# MAIN.net
KiCad netlist of a schematic drawn in Altium Designer
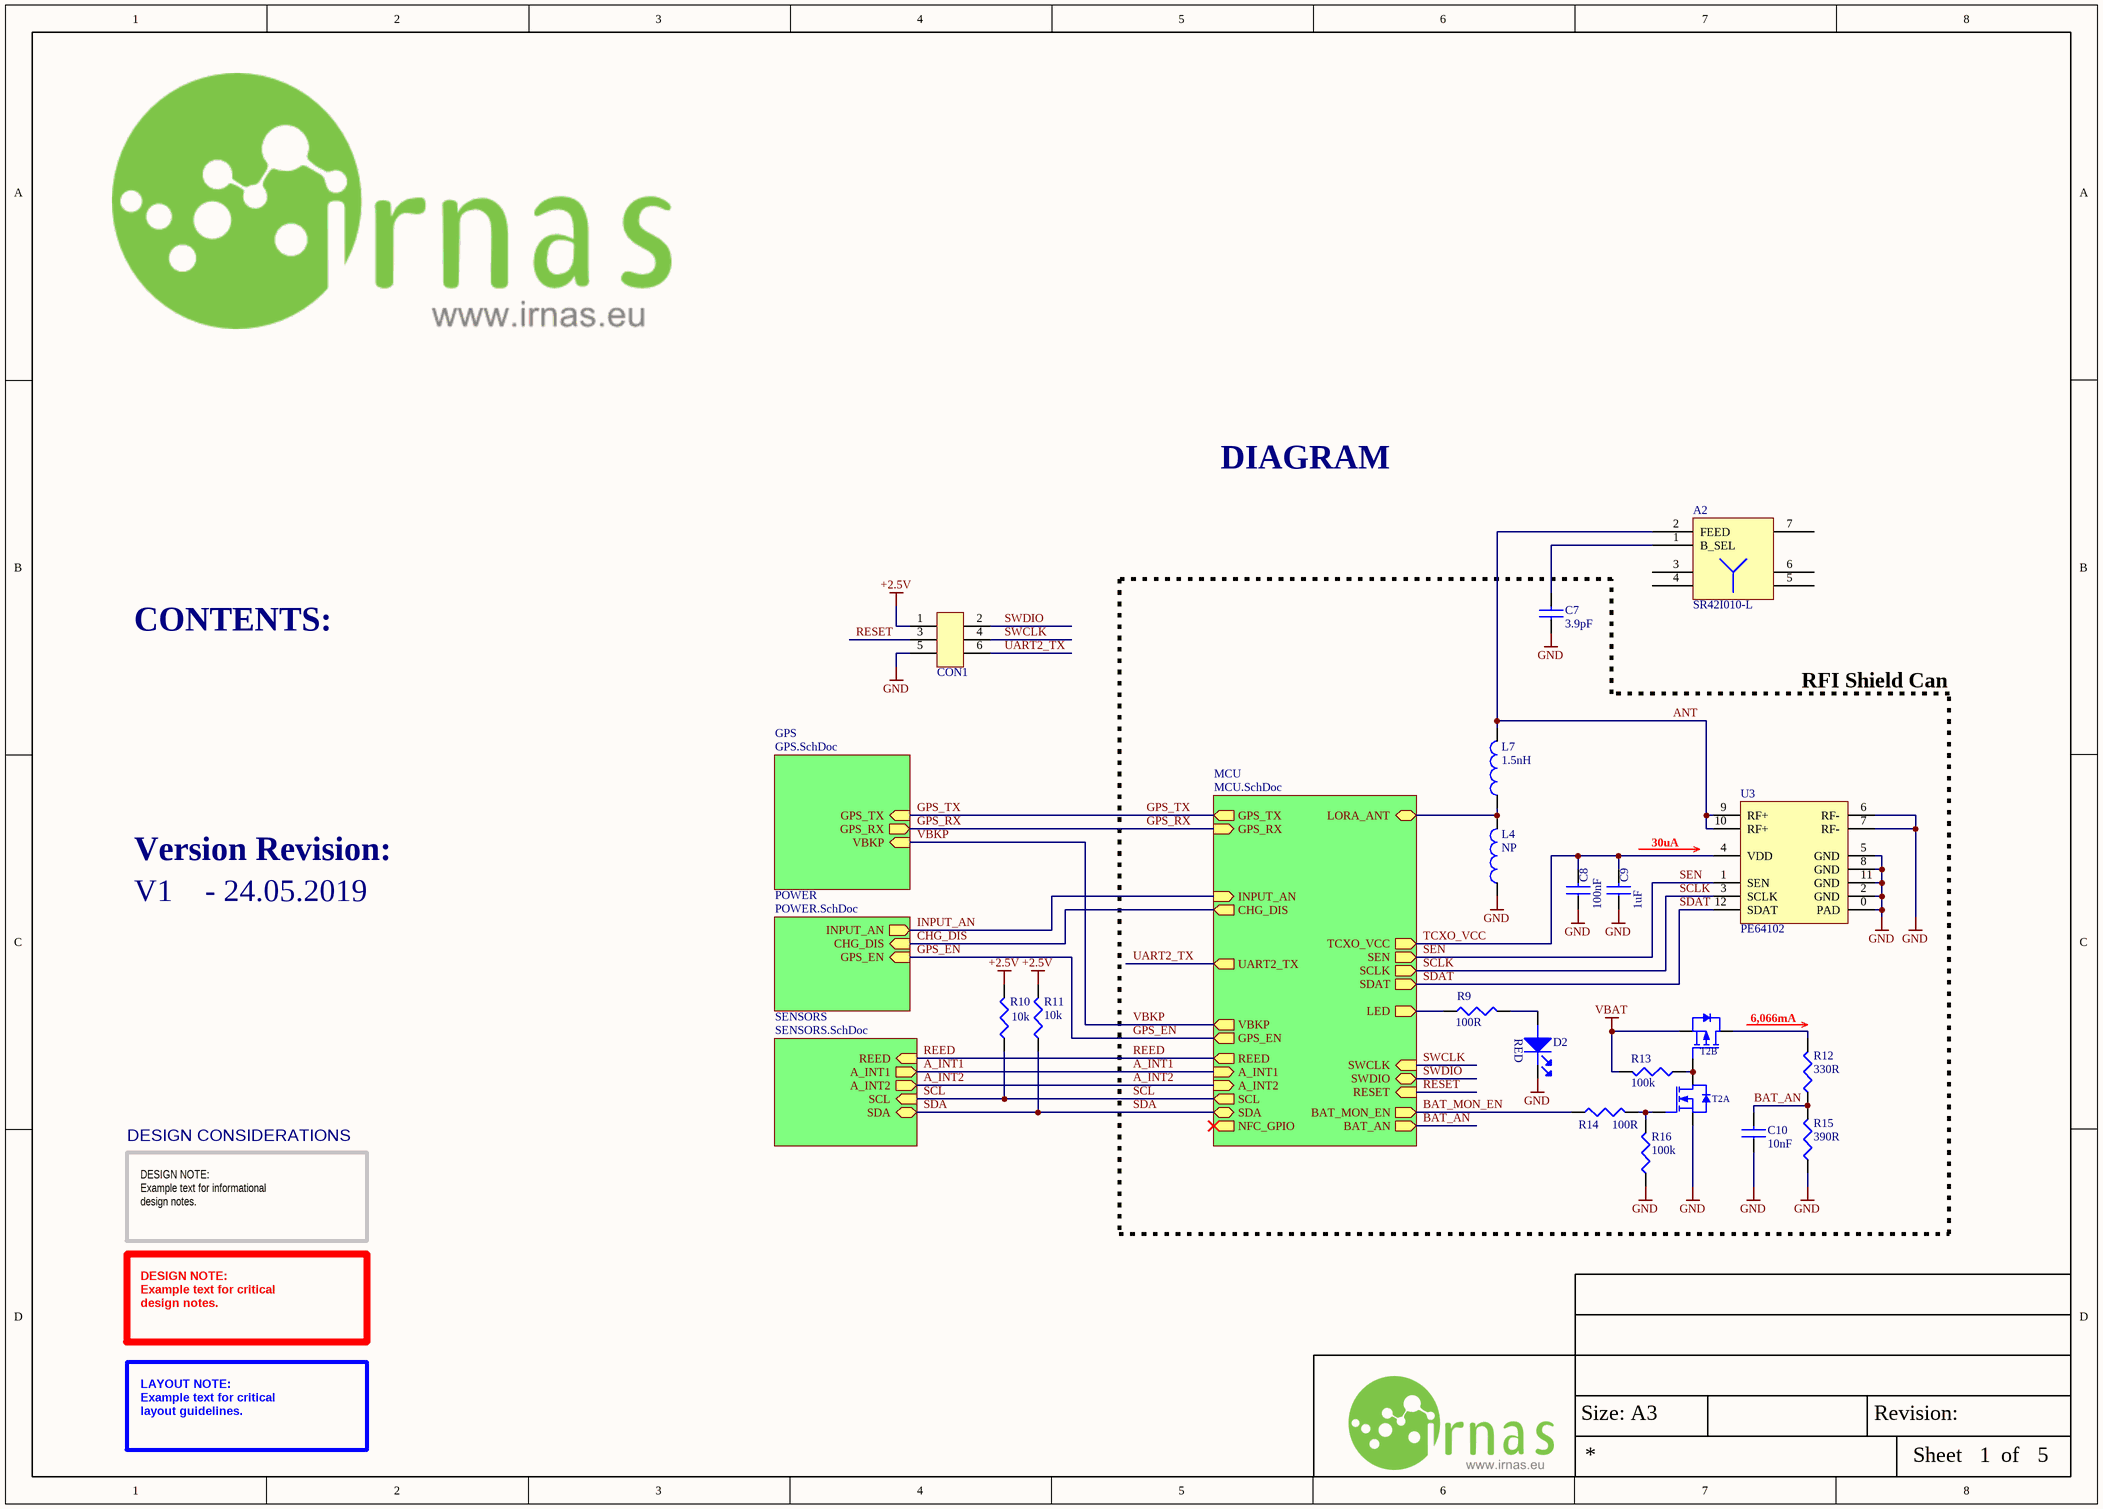
[diagram p0: MAIN.SchDoc]

(export (version "E")
  (design (tool "Eeschema 10.0.6"))
  (components
    (comp (ref "A2")
      (value "SR42I010-L")
      (footprint "SR42I010-L")
      (description "Antenna SMD -4dBi Gain 870MHz/928MHz Automotive 7-Pin SMD T/R")
      (fields (field (name "MANUFACTURER") "Antenova") (field (name "MANUFACTURER PART NUMBER") "SR42I010-R"))
      (libsource (lib "Passive") (part "ANT - SR42I010-L"))
    )
    (comp (ref "C7")
      (value "3.9pF")
      (footprint "CAP0402")
      (description "3.9 pF, 50 V, 0402 [1005 Metric], ± 0.25pF, NP0")
      (fields
        (field (name "MANUFACTURER") "KEMET")
        (field (name "MANUFACTURER PART NUMBER") "MC0402N3R9C500CT")
      )
      (libsource (lib "Passive") (part "C - 3.9pF/0402"))
    )
    (comp (ref "C8")
      (value "100nF")
      (footprint "CAP0402")
      (description "0.1 F, 16 V,  5%, X5R, MC Series")
      (fields
        (field (name "MANUFACTURER") "Multicomp")
        (field (name "MANUFACTURER PART NUMBER") "MC0402X104J160CT")
      )
      (libsource (lib "Passive") (part "C - 100nF/0402"))
    )
    (comp (ref "C9")
      (value "1uF")
      (footprint "CAP0402")
      (description "CAP CER 1UF 10V 20% X5R 0402")
      (fields
        (field (name "MANUFACTURER") "Murata")
        (field (name "MANUFACTURER PART NUMBER") "GRM155R61A105ME15D")
      )
      (libsource (lib "Passive") (part "C - 1uF/0402"))
    )
    (comp (ref "C10")
      (value "10nF")
      (footprint "CAP0402")
      (description "CAP CER 10000PF 16V X7R 0402")
      (fields
        (field (name "MANUFACTURER") "Murata")
        (field (name "MANUFACTURER PART NUMBER") "GRM155R71C103KA01D")
      )
      (libsource (lib "Passive") (part "C - 10nF/0402"))
    )
    (comp (ref "CON1")
      (value "Tag connect")
      (footprint "TC2030-IDC-NL")
      (libsource (lib "Connectors") (part "tag connecot 6 pin"))
    )
    (comp (ref "D2")
      (value "LED RED")
      (footprint "LED0603")
      (description "BROADCOM LIMITED - HSMS-C190 - LED, RED, 10MCD, 626NM")
      (fields
        (field (name "MANUFACTURER") "BROADCOM LIMITED")
        (field (name "MANUFACTURER PART NUMBER") "HSMS-C190")
      )
      (libsource (lib "Active") (part "LED - LED RED"))
    )
    (comp (ref "L4")
      (value "NP")
      (footprint "IND0402")
      (description "Inductor RF Chip Multi-Layer 4.3nH 0.3nH 100MHz 8Q-Factor Air 300mA 210mOhm DCR 0402 Paper T/R")
      (fields
        (field (name "MANUFACTURER") "Murata")
        (field (name "MANUFACTURER PART NUMBER") "LQG15HN4N3S02D")
      )
      (libsource (lib "Passive") (part "L - 4.3nH/0402"))
    )
    (comp (ref "L7")
      (value "1.5nH")
      (footprint "IND0402")
      (description "1.5 nH, LQG15HS_02 Series, 1 A, 0402")
      (fields
        (field (name "MANUFACTURER") "Murata")
        (field (name "MANUFACTURER PART NUMBER") "LQG15HS1N5S02D")
      )
      (libsource (lib "Passive") (part "L - 1.5nH/0402"))
    )
    (comp (ref "R9")
      (value "100R")
      (footprint "RES0402")
      (description "100 ohm, 50 V, 0402 [1005 Metric], 62.5 mW,  1%")
      (fields
        (field (name "MANUFACTURER") "Multicomp")
        (field (name "MANUFACTURER PART NUMBER") "MCMR04X1000FTL")
      )
      (libsource (lib "Passive") (part "R - 100R/0402"))
    )
    (comp (ref "R10")
      (value "10k")
      (footprint "RES0402")
      (description "10 kohm, 50 V, 0402 [1005 Metric], 62.5 mW,  1%, MCWR Series")
      (fields
        (field (name "MANUFACTURER") "Multicomp")
        (field (name "MANUFACTURER PART NUMBER") "MCWR04X1002FTL")
      )
      (libsource (lib "Passive") (part "R - 10k/0402"))
    )
    (comp (ref "R11")
      (value "10k")
      (footprint "RES0402")
      (description "10 kohm, 50 V, 0402 [1005 Metric], 62.5 mW,  1%, MCWR Series")
      (fields
        (field (name "MANUFACTURER") "Multicomp")
        (field (name "MANUFACTURER PART NUMBER") "MCWR04X1002FTL")
      )
      (libsource (lib "Passive") (part "R - 10k/0402"))
    )
    (comp (ref "R12")
      (value "330R")
      (footprint "RES0402")
      (fields
        (field (name "MANUFACTURER") "Multicomp")
        (field (name "MANUFACTURER PART NUMBER") "MCMR04X3300FTL")
        (field (name "TOLERANCE") "1%")
      )
      (libsource (lib "Passive") (part "R - 330R/0402"))
    )
    (comp (ref "R13")
      (value "100k")
      (footprint "RES0402")
      (description "100KOHM, 1%, 0.0625W")
      (fields
        (field (name "MANUFACTURER") "Multicomp")
        (field (name "MANUFACTURER PART NUMBER") "MCWR04X1003FTL")
      )
      (libsource (lib "Passive") (part "R - 100k/0402"))
    )
    (comp (ref "R14")
      (value "100R")
      (footprint "RES0402")
      (description "100 ohm, 50 V, 0402 [1005 Metric], 62.5 mW,  1%")
      (fields
        (field (name "MANUFACTURER") "Multicomp")
        (field (name "MANUFACTURER PART NUMBER") "MCMR04X1000FTL")
      )
      (libsource (lib "Passive") (part "R - 100R/0402"))
    )
    (comp (ref "R15")
      (value "390R")
      (footprint "RES0402")
      (description "390 ohm, MCWR Series, 50 V, Thick Film, 62.5 mW")
      (fields (field (name "MANUFACTURER") "Multicomp") (field (name "MANUFACTURER PART NUMBER") "390/0402"))
      (libsource (lib "Passive") (part "R - 390R/0402"))
    )
    (comp (ref "R16")
      (value "100k")
      (footprint "RES0402")
      (description "100KOHM, 1%, 0.0625W")
      (fields
        (field (name "MANUFACTURER") "Multicomp")
        (field (name "MANUFACTURER PART NUMBER") "MCWR04X1003FTL")
      )
      (libsource (lib "Passive") (part "R - 100k/0402"))
    )
    (comp (ref "T2")
      (value "VT6M1T2CR")
      (footprint "VMT6")
      (description "Dual MOSFET, N and P Channel, 100 mA, 20 V, 2.5 ohm, 4.5 V, 1 V")
      (fields (field (name "AUTHOR") "Ciril Golob"))
      (libsource (lib "Active") (part "T_M - VT6M1T2CR"))
    )
    (comp (ref "U3")
      (value "PE64102")
      (footprint "QFN-12")
      (description "RF IC Digitally Tunable Capacitor General Purpose 100MHz ~ 3GHz SPI Interface 12-QFN (2x2)")
      (fields (field (name "MANUFACTURER") "u-blox") (field (name "MANUFACTURER PART NUMBER") "MAX-M8Q-0"))
      (libsource (lib "Active") (part "RF - PE64102"))
    )
  )
  (nets
    (net (code "1") (name "+2.5V") (class "Default")
      (node (ref "CON1") (pin "1") (pinfunction "1_1") (pintype "open_collector"))
      (node (ref "R10") (pin "2") (pinfunction "2_2") (pintype "passive"))
      (node (ref "R11") (pin "2") (pinfunction "2_2") (pintype "passive"))
    )
    (net (code "2") (name "/ANT") (class "Default")
      (node (ref "A2") (pin "2") (pinfunction "FEED_2") (pintype "passive"))
      (node (ref "L7") (pin "2") (pinfunction "2_2") (pintype "passive"))
      (node (ref "U3") (pin "10") (pinfunction "RF+_10") (pintype "passive"))
      (node (ref "U3") (pin "9") (pinfunction "RF+_9") (pintype "passive"))
    )
    (net (code "5") (name "/BAT_AN") (class "Default")
      (node (ref "C10") (pin "2") (pinfunction "2_2") (pintype "passive"))
      (node (ref "R12") (pin "1") (pinfunction "1_1") (pintype "passive"))
      (node (ref "R15") (pin "2") (pinfunction "2_2") (pintype "passive"))
    )
    (net (code "6") (name "/BAT_MON_EN") (class "Default")
      (node (ref "R14") (pin "1") (pinfunction "1_1") (pintype "passive"))
    )
    (net (code "12") (name "/LED") (class "Default")
      (node (ref "R9") (pin "1") (pinfunction "1_1") (pintype "passive"))
    )
    (net (code "13") (name "/LORA_ANT") (class "Default")
      (node (ref "L4") (pin "2") (pinfunction "2_2") (pintype "passive"))
      (node (ref "L7") (pin "1") (pinfunction "1_1") (pintype "passive"))
    )
    (net (code "16") (name "/RESET") (class "Default")
      (node (ref "CON1") (pin "3") (pinfunction "3_3") (pintype "open_collector"))
    )
    (net (code "17") (name "/SCL") (class "Default")
      (node (ref "R10") (pin "1") (pinfunction "1_1") (pintype "passive"))
    )
    (net (code "18") (name "/SCLK") (class "Default")
      (node (ref "U3") (pin "3") (pinfunction "SCLK_3") (pintype "passive"))
    )
    (net (code "19") (name "/SDA") (class "Default")
      (node (ref "R11") (pin "1") (pinfunction "1_1") (pintype "passive"))
    )
    (net (code "20") (name "/SDAT") (class "Default")
      (node (ref "U3") (pin "12") (pinfunction "SDAT_12") (pintype "passive"))
    )
    (net (code "21") (name "/SEN") (class "Default")
      (node (ref "U3") (pin "1") (pinfunction "SEN_1") (pintype "passive"))
    )
    (net (code "22") (name "/SWCLK") (class "Default")
      (node (ref "CON1") (pin "4") (pinfunction "4_4") (pintype "open_collector"))
    )
    (net (code "23") (name "/SWDIO") (class "Default")
      (node (ref "CON1") (pin "2") (pinfunction "2_2") (pintype "open_collector"))
    )
    (net (code "24") (name "/TCXO_VCC") (class "Default")
      (node (ref "C8") (pin "2") (pinfunction "2_2") (pintype "passive"))
      (node (ref "C9") (pin "2") (pinfunction "2_2") (pintype "passive"))
      (node (ref "U3") (pin "4") (pinfunction "VDD_4") (pintype "passive"))
    )
    (net (code "25") (name "/UART2_TX") (class "Default")
      (node (ref "CON1") (pin "6") (pinfunction "6_6") (pintype "passive"))
    )
    (net (code "27") (name "GND") (class "Default")
      (node (ref "C10") (pin "1") (pinfunction "1_1") (pintype "passive"))
      (node (ref "C7") (pin "1") (pinfunction "1_1") (pintype "passive"))
      (node (ref "C8") (pin "1") (pinfunction "1_1") (pintype "passive"))
      (node (ref "C9") (pin "1") (pinfunction "1_1") (pintype "passive"))
      (node (ref "CON1") (pin "5") (pinfunction "5_5") (pintype "open_collector"))
      (node (ref "D2") (pin "1") (pinfunction "cathode_1") (pintype "passive"))
      (node (ref "L4") (pin "1") (pinfunction "1_1") (pintype "passive"))
      (node (ref "R15") (pin "1") (pinfunction "1_1") (pintype "passive"))
      (node (ref "R16") (pin "1") (pinfunction "1_1") (pintype "passive"))
      (node (ref "T2") (pin "1") (pinfunction "S1_1") (pintype "passive"))
      (node (ref "U3") (pin "0") (pinfunction "PAD_0") (pintype "passive"))
      (node (ref "U3") (pin "11") (pinfunction "GND_11") (pintype "passive"))
      (node (ref "U3") (pin "2") (pinfunction "GND_2") (pintype "passive"))
      (node (ref "U3") (pin "5") (pinfunction "GND_5") (pintype "passive"))
      (node (ref "U3") (pin "6") (pinfunction "RF-_6") (pintype "passive"))
      (node (ref "U3") (pin "7") (pinfunction "RF-_7") (pintype "passive"))
      (node (ref "U3") (pin "8") (pinfunction "GND_8") (pintype "passive"))
    )
    (net (code "28") (name "Net-(A2-B_SEL)") (class "Default")
      (node (ref "A2") (pin "1") (pinfunction "B_SEL_1") (pintype "passive"))
      (node (ref "C7") (pin "2") (pinfunction "2_2") (pintype "passive"))
    )
    (net (code "29") (name "Net-(D2-ANODE)") (class "Default")
      (node (ref "D2") (pin "2") (pinfunction "ANODE_2") (pintype "passive"))
      (node (ref "R9") (pin "2") (pinfunction "2_2") (pintype "passive"))
    )
    (net (code "30") (name "Net-(T2A-D1)") (class "Default")
      (node (ref "R13") (pin "1") (pinfunction "1_1") (pintype "passive"))
      (node (ref "T2") (pin "5") (pinfunction "G2_5") (pintype "passive"))
      (node (ref "T2") (pin "6") (pinfunction "D1_6") (pintype "passive"))
    )
    (net (code "31") (name "Net-(T2A-G1)") (class "Default")
      (node (ref "R14") (pin "2") (pinfunction "2_2") (pintype "passive"))
      (node (ref "R16") (pin "2") (pinfunction "2_2") (pintype "passive"))
      (node (ref "T2") (pin "2") (pinfunction "G1_2") (pintype "passive"))
    )
    (net (code "32") (name "Net-(T2B-D2)") (class "Default")
      (node (ref "R12") (pin "2") (pinfunction "2_2") (pintype "passive"))
      (node (ref "T2") (pin "3") (pinfunction "D2_3") (pintype "passive"))
    )
    (net (code "33") (name "VBAT") (class "Default")
      (node (ref "R13") (pin "2") (pinfunction "2_2") (pintype "passive"))
      (node (ref "T2") (pin "4") (pinfunction "S2_4") (pintype "passive"))
    )
    (net (code "34") (name "unconnected-(A2-Pad3)") (class "Default")
      (node (ref "A2") (pin "3") (pintype "passive"))
    )
    (net (code "35") (name "unconnected-(A2-Pad4)") (class "Default")
      (node (ref "A2") (pin "4") (pintype "passive"))
    )
    (net (code "36") (name "unconnected-(A2-Pad5)") (class "Default")
      (node (ref "A2") (pin "5") (pintype "passive"))
    )
    (net (code "37") (name "unconnected-(A2-Pad6)") (class "Default")
      (node (ref "A2") (pin "6") (pintype "passive"))
    )
    (net (code "38") (name "unconnected-(A2-Pad7)") (class "Default")
      (node (ref "A2") (pin "7") (pintype "passive"))
    )
  )
)
